# CH340G.net
KiCad netlist of a schematic drawn in Altium Designer
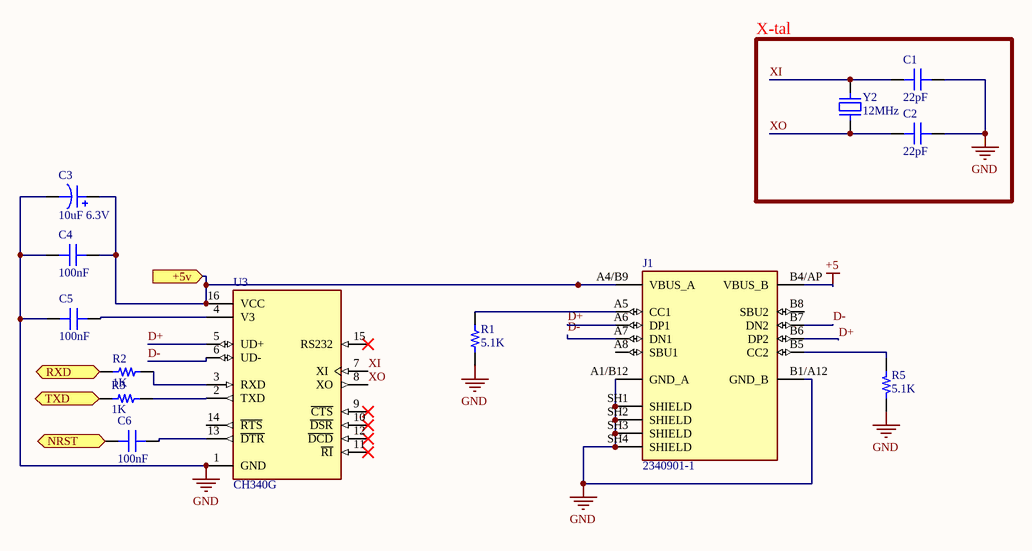
[diagram p0: CH340G.SchDoc]

(export (version "E")
  (design (tool "Eeschema 10.0.6"))
  (components
    (comp (ref "C1")
      (value "22pF")
      (footprint "CAP 0805_2012")
      (description "SMT Capacitor")
      (libsource (lib "Capacitor") (part "Cap 0805"))
    )
    (comp (ref "C2")
      (value "22pF")
      (footprint "CAP 0805_2012")
      (description "SMT Capacitor")
      (libsource (lib "Capacitor") (part "Cap 0805"))
    )
    (comp (ref "C3")
      (value "10uF 6.3V")
      (footprint "CAP ALTH D8 L3.5 H12.5")
      (description "TH Aluminum Polymer Capacitor")
      (libsource (lib "Capacitor") (part "Cap Alu TH D8mm L3.5mm H12.5mm"))
    )
    (comp (ref "C4")
      (value "100nF")
      (footprint "CAP 0805_2012")
      (description "SMT Capacitor")
      (libsource (lib "Capacitor") (part "Cap 0805"))
    )
    (comp (ref "C5")
      (value "100nF")
      (footprint "CAP 0805_2012")
      (description "SMT Capacitor")
      (libsource (lib "Capacitor") (part "Cap 0805"))
    )
    (comp (ref "C6")
      (value "100nF")
      (footprint "CAP 0805_2012")
      (description "SMT Capacitor")
      (libsource (lib "Capacitor") (part "Cap 0805"))
    )
    (comp (ref "J1")
      (value "2340901-1")
      (footprint "TE_2340901-1")
      (description "USB Type C 2.0 Conn Rec Mid-Mount One Ro")
      (fields (field (name "MF") "TE Connectivity"))
      (libsource (lib "2340901-1") (part "2340901-1"))
    )
    (comp (ref "R1")
      (value "5.1K")
      (footprint "RES 0805_2012")
      (description "SMT Resistor")
      (libsource (lib "Resistor") (part "Res 0805"))
    )
    (comp (ref "R2")
      (value "1K")
      (footprint "RES 0805_2012")
      (description "SMT Resistor")
      (libsource (lib "Resistor") (part "Res 0805"))
    )
    (comp (ref "R3")
      (value "1K")
      (footprint "RES 0805_2012")
      (description "SMT Resistor")
      (libsource (lib "Resistor") (part "Res 0805"))
    )
    (comp (ref "R5")
      (value "5.1K")
      (footprint "RES 0805_2012")
      (description "SMT Resistor")
      (libsource (lib "Resistor") (part "Res 0805"))
    )
    (comp (ref "U3")
      (value "CH340G")
      (footprint "SOIC127P600X180-16N")
      (description "USB Interface Integrated Circuit")
      (fields (field (name "MP") "Ch340G") (field (name "MF") "WCH"))
      (libsource (lib "CH340G") (part "CH340G"))
    )
    (comp (ref "Y2")
      (value "12MHz")
      (footprint "HC-49S SMD")
      (description "SMT Crystal")
      (fields (field (name "PARTNUMBER") "ABLS-8.000MHZ-K4T"))
      (libsource (lib "Xtal") (part "Crystal HC-49S SMD 8MHz"))
    )
  )
  (nets
    (net (code "1") (name "+5") (class "Default")
      (node (ref "J1") (pin "B4/AP") (pinfunction "VBUS_B_B4/AP") (pintype "power_in"))
    )
    (net (code "2") (name "/+5v") (class "Default")
      (node (ref "C3") (pin "1") (pinfunction "1_1") (pintype "passive"))
      (node (ref "C4") (pin "1") (pinfunction "1_1") (pintype "passive"))
      (node (ref "J1") (pin "A4/B9") (pinfunction "VBUS_A_A4/B9") (pintype "power_in"))
      (node (ref "U3") (pin "16") (pinfunction "VCC_16") (pintype "power_in"))
    )
    (net (code "3") (name "/D+") (class "Default")
      (node (ref "J1") (pin "A6") (pinfunction "DP1_A6") (pintype "bidirectional"))
      (node (ref "J1") (pin "B6") (pinfunction "DP2_B6") (pintype "bidirectional"))
      (node (ref "U3") (pin "5") (pinfunction "UD+_5") (pintype "bidirectional"))
    )
    (net (code "4") (name "/D-") (class "Default")
      (node (ref "J1") (pin "A7") (pinfunction "DN1_A7") (pintype "bidirectional"))
      (node (ref "J1") (pin "B7") (pinfunction "DN2_B7") (pintype "bidirectional"))
      (node (ref "U3") (pin "6") (pinfunction "UD-_6") (pintype "bidirectional"))
    )
    (net (code "5") (name "/NRST") (class "Default")
      (node (ref "C6") (pin "1") (pinfunction "1_1") (pintype "passive"))
    )
    (net (code "6") (name "/RXD") (class "Default")
      (node (ref "R2") (pin "1") (pinfunction "1_1") (pintype "passive"))
    )
    (net (code "7") (name "/TXD") (class "Default")
      (node (ref "R3") (pin "1") (pinfunction "1_1") (pintype "passive"))
    )
    (net (code "8") (name "/XI") (class "Default")
      (node (ref "C1") (pin "1") (pinfunction "1_1") (pintype "passive"))
      (node (ref "U3") (pin "7") (pinfunction "XI_7") (pintype "input"))
      (node (ref "Y2") (pin "2") (pinfunction "2_2") (pintype "passive"))
    )
    (net (code "9") (name "/XO") (class "Default")
      (node (ref "C2") (pin "1") (pinfunction "1_1") (pintype "passive"))
      (node (ref "U3") (pin "8") (pinfunction "XO_8") (pintype "output"))
      (node (ref "Y2") (pin "1") (pinfunction "1_1") (pintype "passive"))
    )
    (net (code "10") (name "GND") (class "Default")
      (node (ref "C1") (pin "2") (pinfunction "2_2") (pintype "passive"))
      (node (ref "C2") (pin "2") (pinfunction "2_2") (pintype "passive"))
      (node (ref "C3") (pin "2") (pinfunction "2_2") (pintype "passive"))
      (node (ref "C4") (pin "2") (pinfunction "2_2") (pintype "passive"))
      (node (ref "C5") (pin "1") (pinfunction "1_1") (pintype "passive"))
      (node (ref "J1") (pin "A1/B12") (pinfunction "GND_A_A1/B12") (pintype "power_in"))
      (node (ref "J1") (pin "B1/A12") (pinfunction "GND_B_B1/A12") (pintype "power_in"))
      (node (ref "J1") (pin "SH1") (pinfunction "SHIELD_SH1") (pintype "passive"))
      (node (ref "J1") (pin "SH2") (pinfunction "SHIELD_SH2") (pintype "passive"))
      (node (ref "J1") (pin "SH3") (pinfunction "SHIELD_SH3") (pintype "passive"))
      (node (ref "J1") (pin "SH4") (pinfunction "SHIELD_SH4") (pintype "passive"))
      (node (ref "R1") (pin "1") (pinfunction "1_1") (pintype "passive"))
      (node (ref "R5") (pin "1") (pinfunction "1_1") (pintype "passive"))
      (node (ref "U3") (pin "1") (pinfunction "GND_1") (pintype "power_in"))
    )
    (net (code "11") (name "Net-(J1-CC1)") (class "Default")
      (node (ref "J1") (pin "A5") (pinfunction "CC1_A5") (pintype "bidirectional"))
      (node (ref "R1") (pin "2") (pinfunction "2_2") (pintype "passive"))
    )
    (net (code "12") (name "Net-(J1-CC2)") (class "Default")
      (node (ref "J1") (pin "B5") (pinfunction "CC2_B5") (pintype "bidirectional"))
      (node (ref "R5") (pin "2") (pinfunction "2_2") (pintype "passive"))
    )
    (net (code "13") (name "Net-(U3-RXD)") (class "Default")
      (node (ref "R2") (pin "2") (pinfunction "2_2") (pintype "passive"))
      (node (ref "U3") (pin "3") (pinfunction "RXD_3") (pintype "input"))
    )
    (net (code "14") (name "Net-(U3-TXD)") (class "Default")
      (node (ref "R3") (pin "2") (pinfunction "2_2") (pintype "passive"))
      (node (ref "U3") (pin "2") (pinfunction "TXD_2") (pintype "output"))
    )
    (net (code "15") (name "Net-(U3-V3)") (class "Default")
      (node (ref "C5") (pin "2") (pinfunction "2_2") (pintype "passive"))
      (node (ref "U3") (pin "4") (pinfunction "V3_4") (pintype "power_in"))
    )
    (net (code "16") (name "Net-(U3-~{DTR})") (class "Default")
      (node (ref "C6") (pin "2") (pinfunction "2_2") (pintype "passive"))
      (node (ref "U3") (pin "13") (pinfunction "~{DTR}_13") (pintype "output"))
    )
    (net (code "17") (name "unconnected-(J1-SBU1-PadA8)") (class "Default")
      (node (ref "J1") (pin "A8") (pinfunction "SBU1_A8") (pintype "bidirectional"))
    )
    (net (code "18") (name "unconnected-(J1-SBU2-PadB8)") (class "Default")
      (node (ref "J1") (pin "B8") (pinfunction "SBU2_B8") (pintype "bidirectional"))
    )
    (net (code "19") (name "unconnected-(U3-RS232-Pad15)") (class "Default")
      (node (ref "U3") (pin "15") (pinfunction "RS232_15") (pintype "input+no_connect"))
    )
    (net (code "20") (name "unconnected-(U3-~{CTS}-Pad9)") (class "Default")
      (node (ref "U3") (pin "9") (pinfunction "~{CTS}_9") (pintype "input+no_connect"))
    )
    (net (code "21") (name "unconnected-(U3-~{DCD}-Pad12)") (class "Default")
      (node (ref "U3") (pin "12") (pinfunction "~{DCD}_12") (pintype "input+no_connect"))
    )
    (net (code "22") (name "unconnected-(U3-~{DSR}-Pad10)") (class "Default")
      (node (ref "U3") (pin "10") (pinfunction "~{DSR}_10") (pintype "input+no_connect"))
    )
    (net (code "23") (name "unconnected-(U3-~{RI}-Pad11)") (class "Default")
      (node (ref "U3") (pin "11") (pinfunction "~{RI}_11") (pintype "input+no_connect"))
    )
    (net (code "24") (name "unconnected-(U3-~{RTS}-Pad14)") (class "Default")
      (node (ref "U3") (pin "14") (pinfunction "~{RTS}_14") (pintype "output"))
    )
  )
)
